# shield-p1000.net
KiCad netlist of a schematic drawn in EAGLE
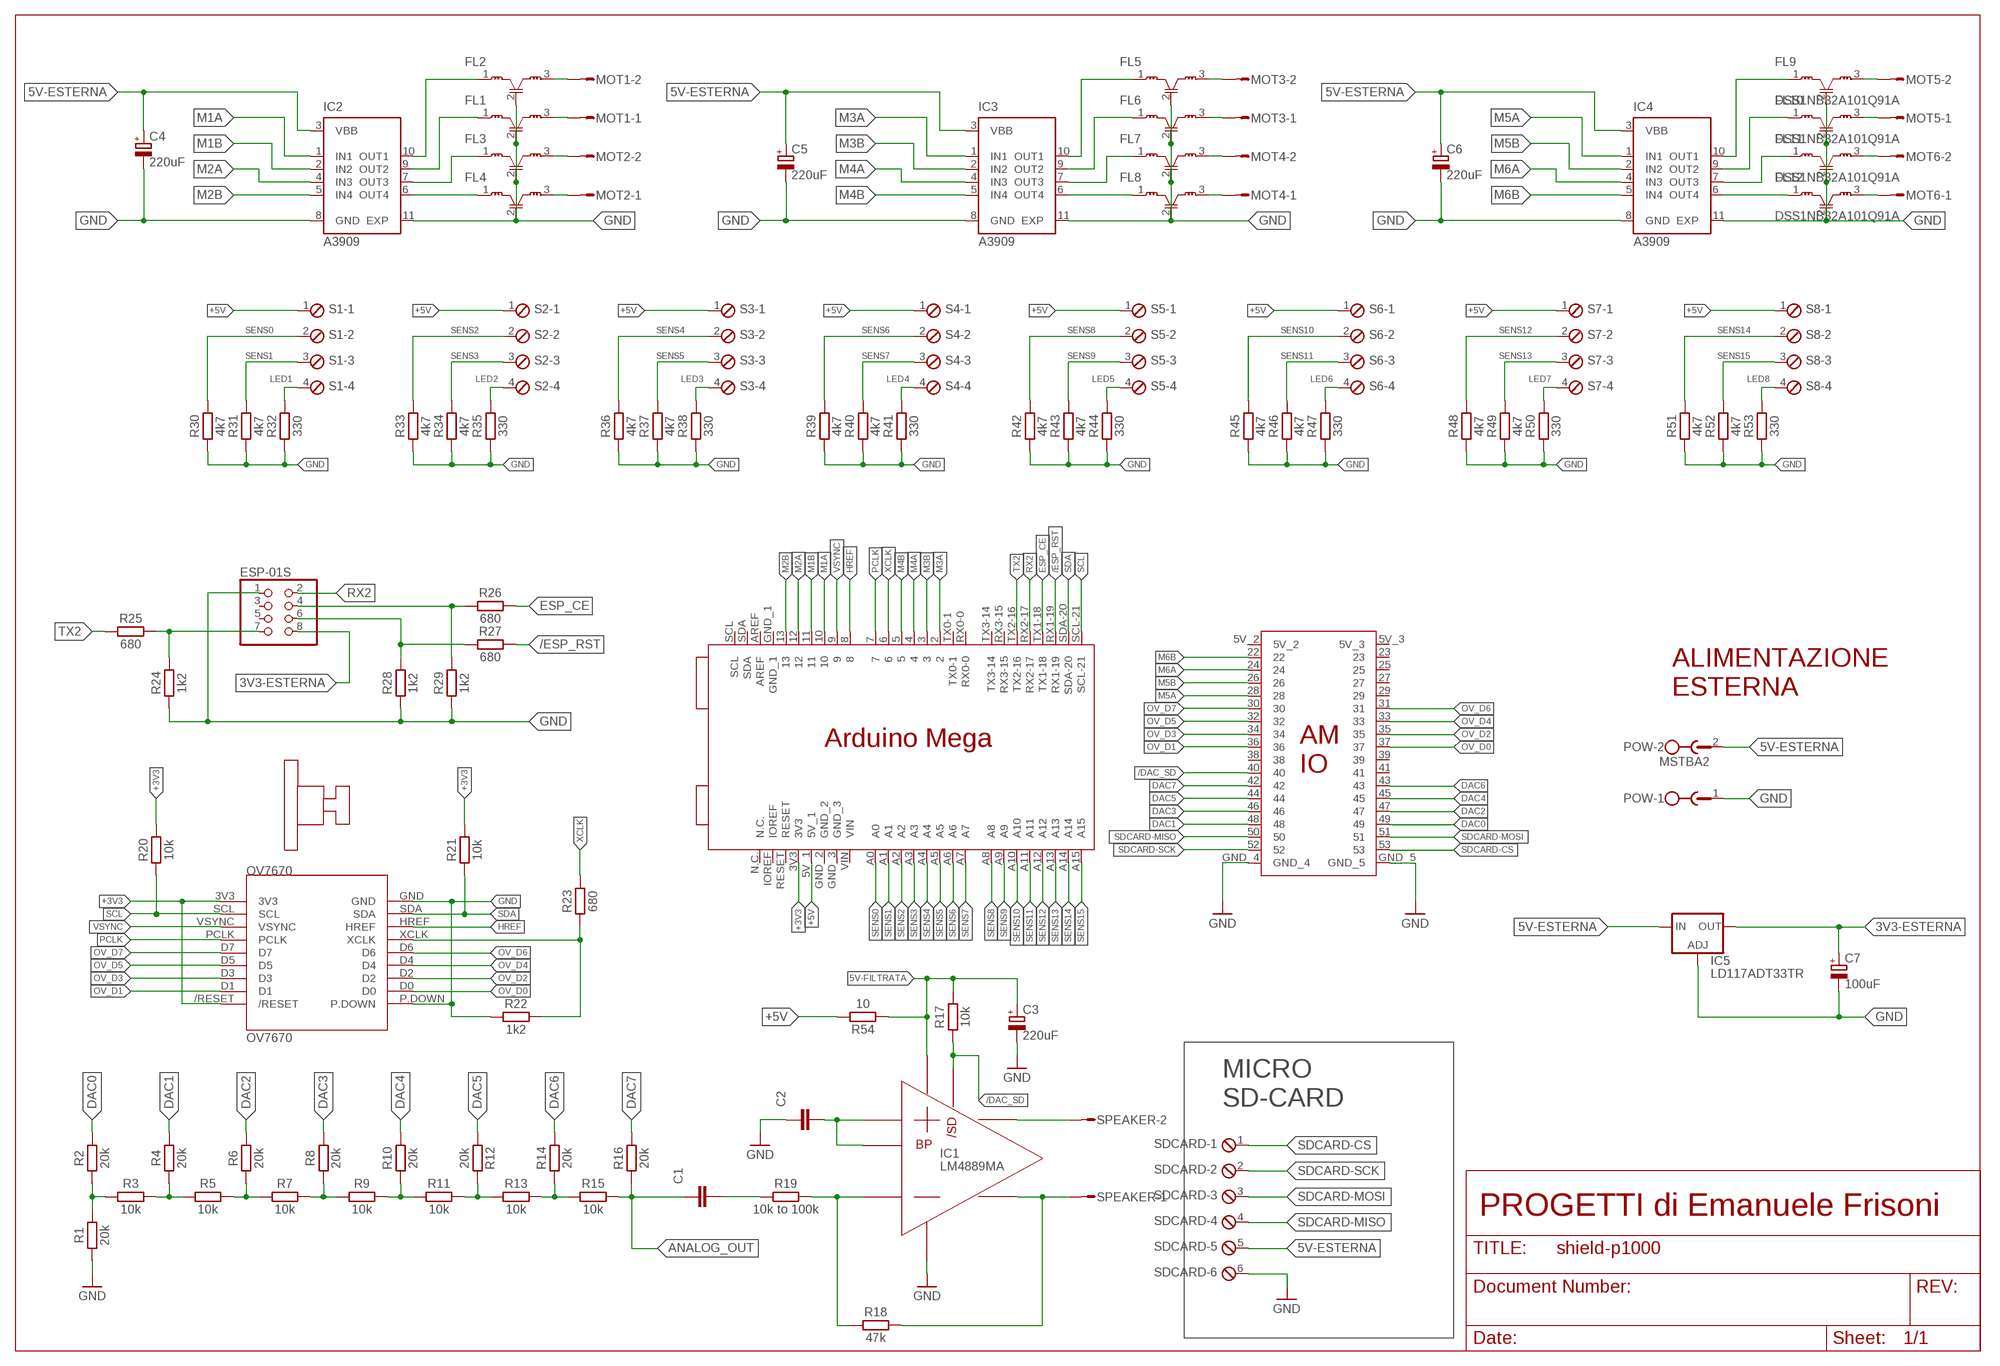
[diagram p0: schematic, sheet 1]

(export (version "E")
  (design (tool "Eeschema 10.0.6"))
  (components
    (comp (ref "ARDUINO-MEGA1")
      (value "ARDUINO-MEGA-SH")
      (footprint "eagle-import:ARDUINO-MEGA-SH")
      (libsource (lib "eagle-import") (part "ARDUINO-MEGA-SH"))
    )
    (comp (ref "C1")
      (value "1uF")
      (footprint "eagle-import:CAPC1608X85")
      (libsource (lib "eagle-import") (part "CCHIP-0603(1608-METRIC)_"))
    )
    (comp (ref "C2")
      (value "1uF")
      (footprint "eagle-import:CAPC1608X85")
      (libsource (lib "eagle-import") (part "CCHIP-0603(1608-METRIC)_"))
    )
    (comp (ref "C3")
      (value "220uF")
      (footprint "eagle-import:E3,5-10")
      (libsource (lib "eagle-import") (part "CPOL-EUE3.5-10"))
    )
    (comp (ref "C4")
      (value "220uF")
      (footprint "eagle-import:E3,5-10")
      (libsource (lib "eagle-import") (part "CPOL-EUE3.5-10"))
    )
    (comp (ref "C5")
      (value "220uF")
      (footprint "eagle-import:E3,5-10")
      (libsource (lib "eagle-import") (part "CPOL-EUE3.5-10"))
    )
    (comp (ref "C6")
      (value "220uF")
      (footprint "eagle-import:E3,5-10")
      (libsource (lib "eagle-import") (part "CPOL-EUE3.5-10"))
    )
    (comp (ref "C7")
      (value "100uF")
      (footprint "eagle-import:E3,5-10")
      (libsource (lib "eagle-import") (part "CPOL-EUE3.5-10"))
    )
    (comp (ref "ESP-01S")
      (value "PINHD-2X4")
      (footprint "eagle-import:2X04")
      (libsource (lib "eagle-import") (part "PINHD-2X4"))
    )
    (comp (ref "FL1")
      (value "DSS1NB32A101Q91A")
      (footprint "eagle-import:RADIAL-3")
      (fields (field (name "MANUFACTURER") "Murata Electronics") (field (name "CREATED_BY") "PCBLayout.com"))
      (libsource (lib "eagle-import") (part "DSS1NB32A101Q91A"))
    )
    (comp (ref "FL2")
      (value "DSS1NB32A101Q91A")
      (footprint "eagle-import:RADIAL-3")
      (fields (field (name "MANUFACTURER") "Murata Electronics") (field (name "CREATED_BY") "PCBLayout.com"))
      (libsource (lib "eagle-import") (part "DSS1NB32A101Q91A"))
    )
    (comp (ref "FL3")
      (value "DSS1NB32A101Q91A")
      (footprint "eagle-import:RADIAL-3")
      (fields (field (name "MANUFACTURER") "Murata Electronics") (field (name "CREATED_BY") "PCBLayout.com"))
      (libsource (lib "eagle-import") (part "DSS1NB32A101Q91A"))
    )
    (comp (ref "FL4")
      (value "DSS1NB32A101Q91A")
      (footprint "eagle-import:RADIAL-3")
      (fields (field (name "MANUFACTURER") "Murata Electronics") (field (name "CREATED_BY") "PCBLayout.com"))
      (libsource (lib "eagle-import") (part "DSS1NB32A101Q91A"))
    )
    (comp (ref "FL5")
      (value "DSS1NB32A101Q91A")
      (footprint "eagle-import:RADIAL-3")
      (fields (field (name "MANUFACTURER") "Murata Electronics") (field (name "CREATED_BY") "PCBLayout.com"))
      (libsource (lib "eagle-import") (part "DSS1NB32A101Q91A"))
    )
    (comp (ref "FL6")
      (value "DSS1NB32A101Q91A")
      (footprint "eagle-import:RADIAL-3")
      (fields (field (name "MANUFACTURER") "Murata Electronics") (field (name "CREATED_BY") "PCBLayout.com"))
      (libsource (lib "eagle-import") (part "DSS1NB32A101Q91A"))
    )
    (comp (ref "FL7")
      (value "DSS1NB32A101Q91A")
      (footprint "eagle-import:RADIAL-3")
      (fields (field (name "MANUFACTURER") "Murata Electronics") (field (name "CREATED_BY") "PCBLayout.com"))
      (libsource (lib "eagle-import") (part "DSS1NB32A101Q91A"))
    )
    (comp (ref "FL8")
      (value "DSS1NB32A101Q91A")
      (footprint "eagle-import:RADIAL-3")
      (fields (field (name "MANUFACTURER") "Murata Electronics") (field (name "CREATED_BY") "PCBLayout.com"))
      (libsource (lib "eagle-import") (part "DSS1NB32A101Q91A"))
    )
    (comp (ref "FL9")
      (value "DSS1NB32A101Q91A")
      (footprint "eagle-import:RADIAL-3")
      (fields (field (name "MANUFACTURER") "Murata Electronics") (field (name "CREATED_BY") "PCBLayout.com"))
      (libsource (lib "eagle-import") (part "DSS1NB32A101Q91A"))
    )
    (comp (ref "FL10")
      (value "DSS1NB32A101Q91A")
      (footprint "eagle-import:RADIAL-3")
      (fields (field (name "MANUFACTURER") "Murata Electronics") (field (name "CREATED_BY") "PCBLayout.com"))
      (libsource (lib "eagle-import") (part "DSS1NB32A101Q91A"))
    )
    (comp (ref "FL11")
      (value "DSS1NB32A101Q91A")
      (footprint "eagle-import:RADIAL-3")
      (fields (field (name "MANUFACTURER") "Murata Electronics") (field (name "CREATED_BY") "PCBLayout.com"))
      (libsource (lib "eagle-import") (part "DSS1NB32A101Q91A"))
    )
    (comp (ref "FL12")
      (value "DSS1NB32A101Q91A")
      (footprint "eagle-import:RADIAL-3")
      (fields (field (name "MANUFACTURER") "Murata Electronics") (field (name "CREATED_BY") "PCBLayout.com"))
      (libsource (lib "eagle-import") (part "DSS1NB32A101Q91A"))
    )
    (comp (ref "IC1")
      (value "LM4889MA")
      (footprint "eagle-import:SOIC127P599X175-8N")
      (libsource (lib "eagle-import") (part "LM4889MA"))
    )
    (comp (ref "IC2")
      (value "A3909")
      (footprint "eagle-import:10-MSOP")
      (libsource (lib "eagle-import") (part "A3909LY"))
    )
    (comp (ref "IC3")
      (value "A3909")
      (footprint "eagle-import:10-MSOP")
      (libsource (lib "eagle-import") (part "A3909LY"))
    )
    (comp (ref "IC4")
      (value "A3909")
      (footprint "eagle-import:10-MSOP")
      (libsource (lib "eagle-import") (part "A3909LY"))
    )
    (comp (ref "IC5")
      (value "LD117ADT33TR")
      (footprint "eagle-import:DPACK")
      (libsource (lib "eagle-import") (part "LD117A?DT33TR"))
    )
    (comp (ref "MOT1")
      (value "S02P")
      (footprint "eagle-import:S02P")
      (libsource (lib "eagle-import") (part "S02P"))
    )
    (comp (ref "MOT2")
      (value "S02P")
      (footprint "eagle-import:S02P")
      (libsource (lib "eagle-import") (part "S02P"))
    )
    (comp (ref "MOT3")
      (value "S02P")
      (footprint "eagle-import:S02P")
      (libsource (lib "eagle-import") (part "S02P"))
    )
    (comp (ref "MOT4")
      (value "S02P")
      (footprint "eagle-import:S02P")
      (libsource (lib "eagle-import") (part "S02P"))
    )
    (comp (ref "MOT5")
      (value "S02P")
      (footprint "eagle-import:S02P")
      (libsource (lib "eagle-import") (part "S02P"))
    )
    (comp (ref "MOT6")
      (value "S02P")
      (footprint "eagle-import:S02P")
      (libsource (lib "eagle-import") (part "S02P"))
    )
    (comp (ref "OV7670")
      (value "OV7670")
      (footprint "eagle-import:OV7670-HEADER")
      (libsource (lib "eagle-import") (part "OV7670"))
    )
    (comp (ref "POW")
      (value "MSTBA2")
      (footprint "eagle-import:MSTBA2")
      (fields (field (name "MF") "FARNELL") (field (name "MPN") "1757242"))
      (libsource (lib "eagle-import") (part "MSTBA2"))
    )
    (comp (ref "R1")
      (value "20k")
      (footprint "eagle-import:RESC1608X60")
      (libsource (lib "eagle-import") (part "RCHIP-0603(1608-METRIC)_"))
    )
    (comp (ref "R2")
      (value "20k")
      (footprint "eagle-import:RESC1608X60")
      (libsource (lib "eagle-import") (part "RCHIP-0603(1608-METRIC)_"))
    )
    (comp (ref "R3")
      (value "10k")
      (footprint "eagle-import:RESC1608X60")
      (libsource (lib "eagle-import") (part "RCHIP-0603(1608-METRIC)_"))
    )
    (comp (ref "R4")
      (value "20k")
      (footprint "eagle-import:RESC1608X60")
      (libsource (lib "eagle-import") (part "RCHIP-0603(1608-METRIC)_"))
    )
    (comp (ref "R5")
      (value "10k")
      (footprint "eagle-import:RESC1608X60")
      (libsource (lib "eagle-import") (part "RCHIP-0603(1608-METRIC)_"))
    )
    (comp (ref "R6")
      (value "20k")
      (footprint "eagle-import:RESC1608X60")
      (libsource (lib "eagle-import") (part "RCHIP-0603(1608-METRIC)_"))
    )
    (comp (ref "R7")
      (value "10k")
      (footprint "eagle-import:RESC1608X60")
      (libsource (lib "eagle-import") (part "RCHIP-0603(1608-METRIC)_"))
    )
    (comp (ref "R8")
      (value "20k")
      (footprint "eagle-import:RESC1608X60")
      (libsource (lib "eagle-import") (part "RCHIP-0603(1608-METRIC)_"))
    )
    (comp (ref "R9")
      (value "10k")
      (footprint "eagle-import:RESC1608X60")
      (libsource (lib "eagle-import") (part "RCHIP-0603(1608-METRIC)_"))
    )
    (comp (ref "R10")
      (value "20k")
      (footprint "eagle-import:RESC1608X60")
      (libsource (lib "eagle-import") (part "RCHIP-0603(1608-METRIC)_"))
    )
    (comp (ref "R11")
      (value "10k")
      (footprint "eagle-import:RESC1608X60")
      (libsource (lib "eagle-import") (part "RCHIP-0603(1608-METRIC)_"))
    )
    (comp (ref "R12")
      (value "20k")
      (footprint "eagle-import:RESC1608X60")
      (libsource (lib "eagle-import") (part "RCHIP-0603(1608-METRIC)_"))
    )
    (comp (ref "R13")
      (value "10k")
      (footprint "eagle-import:RESC1608X60")
      (libsource (lib "eagle-import") (part "RCHIP-0603(1608-METRIC)_"))
    )
    (comp (ref "R14")
      (value "20k")
      (footprint "eagle-import:RESC1608X60")
      (libsource (lib "eagle-import") (part "RCHIP-0603(1608-METRIC)_"))
    )
    (comp (ref "R15")
      (value "10k")
      (footprint "eagle-import:RESC1608X60")
      (libsource (lib "eagle-import") (part "RCHIP-0603(1608-METRIC)_"))
    )
    (comp (ref "R16")
      (value "20k")
      (footprint "eagle-import:RESC1608X60")
      (libsource (lib "eagle-import") (part "RCHIP-0603(1608-METRIC)_"))
    )
    (comp (ref "R17")
      (value "10k")
      (footprint "eagle-import:RESC1608X60")
      (libsource (lib "eagle-import") (part "RCHIP-0603(1608-METRIC)_"))
    )
    (comp (ref "R18")
      (value "47k")
      (footprint "eagle-import:RESC1608X60")
      (libsource (lib "eagle-import") (part "RCHIP-0603(1608-METRIC)_"))
    )
    (comp (ref "R19")
      (value "10k to 100k")
      (footprint "eagle-import:RESAD724W46L381D178B")
      (libsource (lib "eagle-import") (part "RAXIAL-7.2MM-PITCH_"))
    )
    (comp (ref "R20")
      (value "10k")
      (footprint "eagle-import:RESC1608X60")
      (libsource (lib "eagle-import") (part "RCHIP-0603(1608-METRIC)_"))
    )
    (comp (ref "R21")
      (value "10k")
      (footprint "eagle-import:RESC1608X60")
      (libsource (lib "eagle-import") (part "RCHIP-0603(1608-METRIC)_"))
    )
    (comp (ref "R22")
      (value "1k2")
      (footprint "eagle-import:RESC1608X60")
      (libsource (lib "eagle-import") (part "RCHIP-0603(1608-METRIC)_"))
    )
    (comp (ref "R23")
      (value "680")
      (footprint "eagle-import:RESC1608X60")
      (libsource (lib "eagle-import") (part "RCHIP-0603(1608-METRIC)_"))
    )
    (comp (ref "R24")
      (value "1k2")
      (footprint "eagle-import:RESC1608X60")
      (libsource (lib "eagle-import") (part "RCHIP-0603(1608-METRIC)_"))
    )
    (comp (ref "R25")
      (value "680")
      (footprint "eagle-import:RESC1608X60")
      (libsource (lib "eagle-import") (part "RCHIP-0603(1608-METRIC)_"))
    )
    (comp (ref "R26")
      (value "680")
      (footprint "eagle-import:RESC1608X60")
      (libsource (lib "eagle-import") (part "RCHIP-0603(1608-METRIC)_"))
    )
    (comp (ref "R27")
      (value "680")
      (footprint "eagle-import:RESC1608X60")
      (libsource (lib "eagle-import") (part "RCHIP-0603(1608-METRIC)_"))
    )
    (comp (ref "R28")
      (value "1k2")
      (footprint "eagle-import:RESC1608X60")
      (libsource (lib "eagle-import") (part "RCHIP-0603(1608-METRIC)_"))
    )
    (comp (ref "R29")
      (value "1k2")
      (footprint "eagle-import:RESC1608X60")
      (libsource (lib "eagle-import") (part "RCHIP-0603(1608-METRIC)_"))
    )
    (comp (ref "R30")
      (value "4k7")
      (footprint "eagle-import:RESC1608X60")
      (libsource (lib "eagle-import") (part "RCHIP-0603(1608-METRIC)_"))
    )
    (comp (ref "R31")
      (value "4k7")
      (footprint "eagle-import:RESC1608X60")
      (libsource (lib "eagle-import") (part "RCHIP-0603(1608-METRIC)_"))
    )
    (comp (ref "R32")
      (value "330")
      (footprint "eagle-import:RESC1608X60")
      (libsource (lib "eagle-import") (part "RCHIP-0603(1608-METRIC)_"))
    )
    (comp (ref "R33")
      (value "4k7")
      (footprint "eagle-import:RESC1608X60")
      (libsource (lib "eagle-import") (part "RCHIP-0603(1608-METRIC)_"))
    )
    (comp (ref "R34")
      (value "4k7")
      (footprint "eagle-import:RESC1608X60")
      (libsource (lib "eagle-import") (part "RCHIP-0603(1608-METRIC)_"))
    )
    (comp (ref "R35")
      (value "330")
      (footprint "eagle-import:RESC1608X60")
      (libsource (lib "eagle-import") (part "RCHIP-0603(1608-METRIC)_"))
    )
    (comp (ref "R36")
      (value "4k7")
      (footprint "eagle-import:RESC1608X60")
      (libsource (lib "eagle-import") (part "RCHIP-0603(1608-METRIC)_"))
    )
    (comp (ref "R37")
      (value "4k7")
      (footprint "eagle-import:RESC1608X60")
      (libsource (lib "eagle-import") (part "RCHIP-0603(1608-METRIC)_"))
    )
    (comp (ref "R38")
      (value "330")
      (footprint "eagle-import:RESC1608X60")
      (libsource (lib "eagle-import") (part "RCHIP-0603(1608-METRIC)_"))
    )
    (comp (ref "R39")
      (value "4k7")
      (footprint "eagle-import:RESC1608X60")
      (libsource (lib "eagle-import") (part "RCHIP-0603(1608-METRIC)_"))
    )
    (comp (ref "R40")
      (value "4k7")
      (footprint "eagle-import:RESC1608X60")
      (libsource (lib "eagle-import") (part "RCHIP-0603(1608-METRIC)_"))
    )
    (comp (ref "R41")
      (value "330")
      (footprint "eagle-import:RESC1608X60")
      (libsource (lib "eagle-import") (part "RCHIP-0603(1608-METRIC)_"))
    )
    (comp (ref "R42")
      (value "4k7")
      (footprint "eagle-import:RESC1608X60")
      (libsource (lib "eagle-import") (part "RCHIP-0603(1608-METRIC)_"))
    )
    (comp (ref "R43")
      (value "4k7")
      (footprint "eagle-import:RESC1608X60")
      (libsource (lib "eagle-import") (part "RCHIP-0603(1608-METRIC)_"))
    )
    (comp (ref "R44")
      (value "330")
      (footprint "eagle-import:RESC1608X60")
      (libsource (lib "eagle-import") (part "RCHIP-0603(1608-METRIC)_"))
    )
    (comp (ref "R45")
      (value "4k7")
      (footprint "eagle-import:RESC1608X60")
      (libsource (lib "eagle-import") (part "RCHIP-0603(1608-METRIC)_"))
    )
    (comp (ref "R46")
      (value "4k7")
      (footprint "eagle-import:RESC1608X60")
      (libsource (lib "eagle-import") (part "RCHIP-0603(1608-METRIC)_"))
    )
    (comp (ref "R47")
      (value "330")
      (footprint "eagle-import:RESC1608X60")
      (libsource (lib "eagle-import") (part "RCHIP-0603(1608-METRIC)_"))
    )
    (comp (ref "R48")
      (value "4k7")
      (footprint "eagle-import:RESC1608X60")
      (libsource (lib "eagle-import") (part "RCHIP-0603(1608-METRIC)_"))
    )
    (comp (ref "R49")
      (value "4k7")
      (footprint "eagle-import:RESC1608X60")
      (libsource (lib "eagle-import") (part "RCHIP-0603(1608-METRIC)_"))
    )
    (comp (ref "R50")
      (value "330")
      (footprint "eagle-import:RESC1608X60")
      (libsource (lib "eagle-import") (part "RCHIP-0603(1608-METRIC)_"))
    )
    (comp (ref "R51")
      (value "4k7")
      (footprint "eagle-import:RESC1608X60")
      (libsource (lib "eagle-import") (part "RCHIP-0603(1608-METRIC)_"))
    )
    (comp (ref "R52")
      (value "4k7")
      (footprint "eagle-import:RESC1608X60")
      (libsource (lib "eagle-import") (part "RCHIP-0603(1608-METRIC)_"))
    )
    (comp (ref "R53")
      (value "330")
      (footprint "eagle-import:RESC1608X60")
      (libsource (lib "eagle-import") (part "RCHIP-0603(1608-METRIC)_"))
    )
    (comp (ref "R54")
      (value "10")
      (footprint "eagle-import:RESC1608X60")
      (libsource (lib "eagle-import") (part "RCHIP-0603(1608-METRIC)_"))
    )
    (comp (ref "S1")
      (value "MPT4")
      (footprint "eagle-import:4POL254")
      (libsource (lib "eagle-import") (part "MPT4"))
    )
    (comp (ref "S2")
      (value "MPT4")
      (footprint "eagle-import:4POL254")
      (libsource (lib "eagle-import") (part "MPT4"))
    )
    (comp (ref "S3")
      (value "MPT4")
      (footprint "eagle-import:4POL254")
      (libsource (lib "eagle-import") (part "MPT4"))
    )
    (comp (ref "S4")
      (value "MPT4")
      (footprint "eagle-import:4POL254")
      (libsource (lib "eagle-import") (part "MPT4"))
    )
    (comp (ref "S5")
      (value "MPT4")
      (footprint "eagle-import:4POL254")
      (libsource (lib "eagle-import") (part "MPT4"))
    )
    (comp (ref "S6")
      (value "MPT4")
      (footprint "eagle-import:4POL254")
      (libsource (lib "eagle-import") (part "MPT4"))
    )
    (comp (ref "S7")
      (value "MPT4")
      (footprint "eagle-import:4POL254")
      (libsource (lib "eagle-import") (part "MPT4"))
    )
    (comp (ref "S8")
      (value "MPT4")
      (footprint "eagle-import:4POL254")
      (libsource (lib "eagle-import") (part "MPT4"))
    )
    (comp (ref "SDCARD")
      (value "MPT6")
      (footprint "eagle-import:6POL254")
      (libsource (lib "eagle-import") (part "MPT6"))
    )
    (comp (ref "SPEAKER")
      (value "S02P")
      (footprint "eagle-import:S02P")
      (libsource (lib "eagle-import") (part "S02P"))
    )
  )
  (nets
    (net (code "1") (name "+3V3") (class "Default")
      (node (ref "ARDUINO-MEGA1") (pin "3V3") (pinfunction "3V3_3V3") (pintype "bidirectional"))
      (node (ref "OV7670") (pin "/RESET") (pinfunction "/RESET_/RESET") (pintype "bidirectional"))
      (node (ref "OV7670") (pin "3V3") (pinfunction "3V3_3V3") (pintype "bidirectional"))
      (node (ref "R20") (pin "2") (pinfunction "2_2") (pintype "passive"))
      (node (ref "R21") (pin "2") (pinfunction "2_2") (pintype "passive"))
    )
    (net (code "2") (name "+5V") (class "Default")
      (node (ref "ARDUINO-MEGA1") (pin "5V_1") (pinfunction "5V_1_5V_1") (pintype "bidirectional"))
      (node (ref "R54") (pin "1") (pinfunction "1_1") (pintype "passive"))
      (node (ref "S1") (pin "1") (pinfunction "1_1") (pintype "passive"))
      (node (ref "S2") (pin "1") (pinfunction "1_1") (pintype "passive"))
      (node (ref "S3") (pin "1") (pinfunction "1_1") (pintype "passive"))
      (node (ref "S4") (pin "1") (pinfunction "1_1") (pintype "passive"))
      (node (ref "S5") (pin "1") (pinfunction "1_1") (pintype "passive"))
      (node (ref "S6") (pin "1") (pinfunction "1_1") (pintype "passive"))
      (node (ref "S7") (pin "1") (pinfunction "1_1") (pintype "passive"))
      (node (ref "S8") (pin "1") (pinfunction "1_1") (pintype "passive"))
    )
    (net (code "3") (name "/LED1") (class "Default")
      (node (ref "R32") (pin "2") (pinfunction "2_2") (pintype "passive"))
      (node (ref "S1") (pin "4") (pinfunction "1_4") (pintype "passive"))
    )
    (net (code "4") (name "/LED2") (class "Default")
      (node (ref "R35") (pin "2") (pinfunction "2_2") (pintype "passive"))
      (node (ref "S2") (pin "4") (pinfunction "1_4") (pintype "passive"))
    )
    (net (code "5") (name "/LED3") (class "Default")
      (node (ref "R38") (pin "2") (pinfunction "2_2") (pintype "passive"))
      (node (ref "S3") (pin "4") (pinfunction "1_4") (pintype "passive"))
    )
    (net (code "6") (name "/LED4") (class "Default")
      (node (ref "R41") (pin "2") (pinfunction "2_2") (pintype "passive"))
      (node (ref "S4") (pin "4") (pinfunction "1_4") (pintype "passive"))
    )
    (net (code "7") (name "/LED5") (class "Default")
      (node (ref "R44") (pin "2") (pinfunction "2_2") (pintype "passive"))
      (node (ref "S5") (pin "4") (pinfunction "1_4") (pintype "passive"))
    )
    (net (code "8") (name "/LED6") (class "Default")
      (node (ref "R47") (pin "2") (pinfunction "2_2") (pintype "passive"))
      (node (ref "S6") (pin "4") (pinfunction "1_4") (pintype "passive"))
    )
    (net (code "9") (name "/LED7") (class "Default")
      (node (ref "R50") (pin "2") (pinfunction "2_2") (pintype "passive"))
      (node (ref "S7") (pin "4") (pinfunction "1_4") (pintype "passive"))
    )
    (net (code "10") (name "/LED8") (class "Default")
      (node (ref "R53") (pin "2") (pinfunction "2_2") (pintype "passive"))
      (node (ref "S8") (pin "4") (pinfunction "1_4") (pintype "passive"))
    )
    (net (code "11") (name "3V3-ESTERNA") (class "Default")
      (node (ref "C7") (pin "+") (pinfunction "+_+") (pintype "passive"))
      (node (ref "ESP-01S") (pin "8") (pinfunction "8_8") (pintype "passive"))
      (node (ref "IC5") (pin "4") (pinfunction "OUT_4") (pintype "passive"))
    )
    (net (code "12") (name "5V-ESTERNA") (class "Default")
      (node (ref "C4") (pin "+") (pinfunction "+_+") (pintype "passive"))
      (node (ref "C5") (pin "+") (pinfunction "+_+") (pintype "passive"))
      (node (ref "C6") (pin "+") (pinfunction "+_+") (pintype "passive"))
      (node (ref "IC2") (pin "3") (pinfunction "VBB_3") (pintype "power_in"))
      (node (ref "IC3") (pin "3") (pinfunction "VBB_3") (pintype "power_in"))
      (node (ref "IC4") (pin "3") (pinfunction "VBB_3") (pintype "power_in"))
      (node (ref "IC5") (pin "3") (pinfunction "IN_3") (pintype "input"))
      (node (ref "POW") (pin "2") (pinfunction "1_2") (pintype "passive"))
      (node (ref "SDCARD") (pin "5") (pinfunction "1_5") (pintype "passive"))
    )
    (net (code "13") (name "5V-FILTRATA") (class "Default")
      (node (ref "C3") (pin "+") (pinfunction "+_+") (pintype "passive"))
      (node (ref "IC1") (pin "6") (pinfunction "VDD_6") (pintype "bidirectional"))
      (node (ref "R17") (pin "1") (pinfunction "1_1") (pintype "passive"))
      (node (ref "R54") (pin "2") (pinfunction "2_2") (pintype "passive"))
    )
    (net (code "14") (name "ANALOG_OUT") (class "Default")
      (node (ref "C1") (pin "1") (pinfunction "1_1") (pintype "passive"))
      (node (ref "R15") (pin "1") (pinfunction "1_1") (pintype "passive"))
      (node (ref "R16") (pin "2") (pinfunction "2_2") (pintype "passive"))
    )
    (net (code "15") (name "DAC0") (class "Default")
      (node (ref "ARDUINO-MEGA1") (pin "49") (pinfunction "49_49") (pintype "bidirectional"))
      (node (ref "R2") (pin "1") (pinfunction "1_1") (pintype "passive"))
    )
    (net (code "16") (name "DAC1") (class "Default")
      (node (ref "ARDUINO-MEGA1") (pin "48") (pinfunction "48_48") (pintype "bidirectional"))
      (node (ref "R4") (pin "1") (pinfunction "1_1") (pintype "passive"))
    )
    (net (code "17") (name "DAC2") (class "Default")
      (node (ref "ARDUINO-MEGA1") (pin "47") (pinfunction "47_47") (pintype "bidirectional"))
      (node (ref "R6") (pin "1") (pinfunction "1_1") (pintype "passive"))
    )
    (net (code "18") (name "DAC3") (class "Default")
      (node (ref "ARDUINO-MEGA1") (pin "46") (pinfunction "46_46") (pintype "bidirectional"))
      (node (ref "R8") (pin "1") (pinfunction "1_1") (pintype "passive"))
    )
    (net (code "19") (name "DAC4") (class "Default")
      (node (ref "ARDUINO-MEGA1") (pin "45") (pinfunction "45_45") (pintype "bidirectional"))
      (node (ref "R10") (pin "1") (pinfunction "1_1") (pintype "passive"))
    )
    (net (code "20") (name "DAC5") (class "Default")
      (node (ref "ARDUINO-MEGA1") (pin "44") (pinfunction "44_44") (pintype "bidirectional"))
      (node (ref "R12") (pin "1") (pinfunction "1_1") (pintype "passive"))
    )
    (net (code "21") (name "DAC6") (class "Default")
      (node (ref "ARDUINO-MEGA1") (pin "43") (pinfunction "43_43") (pintype "bidirectional"))
      (node (ref "R14") (pin "1") (pinfunction "1_1") (pintype "passive"))
    )
    (net (code "22") (name "DAC7") (class "Default")
      (node (ref "ARDUINO-MEGA1") (pin "42") (pinfunction "42_42") (pintype "bidirectional"))
      (node (ref "R16") (pin "1") (pinfunction "1_1") (pintype "passive"))
    )
    (net (code "23") (name "ESP_CE") (class "Default")
      (node (ref "ARDUINO-MEGA1") (pin "TX1-18") (pinfunction "TX1-18_TX1-18") (pintype "bidirectional"))
      (node (ref "R26") (pin "2") (pinfunction "2_2") (pintype "passive"))
    )
    (net (code "24") (name "GND") (class "Default")
      (node (ref "ARDUINO-MEGA1") (pin "GND_4") (pinfunction "GND_4_GND_4") (pintype "bidirectional"))
      (node (ref "ARDUINO-MEGA1") (pin "GND_5") (pinfunction "GND_5_GND_5") (pintype "bidirectional"))
      (node (ref "C2") (pin "1") (pinfunction "1_1") (pintype "passive"))
      (node (ref "C3") (pin "-") (pinfunction "-_-") (pintype "passive"))
      (node (ref "C4") (pin "-") (pinfunction "-_-") (pintype "passive"))
      (node (ref "C5") (pin "-") (pinfunction "-_-") (pintype "passive"))
      (node (ref "C6") (pin "-") (pinfunction "-_-") (pintype "passive"))
      (node (ref "C7") (pin "-") (pinfunction "-_-") (pintype "passive"))
      (node (ref "ESP-01S") (pin "1") (pinfunction "1_1") (pintype "passive"))
      (node (ref "FL1") (pin "2") (pinfunction "GND_2") (pintype "passive"))
      (node (ref "FL10") (pin "2") (pinfunction "GND_2") (pintype "passive"))
      (node (ref "FL11") (pin "2") (pinfunction "GND_2") (pintype "passive"))
      (node (ref "FL12") (pin "2") (pinfunction "GND_2") (pintype "passive"))
      (node (ref "FL2") (pin "2") (pinfunction "GND_2") (pintype "passive"))
      (node (ref "FL3") (pin "2") (pinfunction "GND_2") (pintype "passive"))
      (node (ref "FL4") (pin "2") (pinfunction "GND_2") (pintype "passive"))
      (node (ref "FL5") (pin "2") (pinfunction "GND_2") (pintype "passive"))
      (node (ref "FL6") (pin "2") (pinfunction "GND_2") (pintype "passive"))
      (node (ref "FL7") (pin "2") (pinfunction "GND_2") (pintype "passive"))
      (node (ref "FL8") (pin "2") (pinfunction "GND_2") (pintype "passive"))
      (node (ref "FL9") (pin "2") (pinfunction "GND_2") (pintype "passive"))
      (node (ref "IC1") (pin "7") (pinfunction "VSS_7") (pintype "bidirectional"))
      (node (ref "IC2") (pin "11") (pinfunction "EXP_11") (pintype "passive"))
      (node (ref "IC2") (pin "8") (pinfunction "GND_8") (pintype "power_in"))
      (node (ref "IC3") (pin "11") (pinfunction "EXP_11") (pintype "passive"))
      (node (ref "IC3") (pin "8") (pinfunction "GND_8") (pintype "power_in"))
      (node (ref "IC4") (pin "11") (pinfunction "EXP_11") (pintype "passive"))
      (node (ref "IC4") (pin "8") (pinfunction "GND_8") (pintype "power_in"))
      (node (ref "IC5") (pin "1") (pinfunction "ADJ_1") (pintype "input"))
      (node (ref "OV7670") (pin "GND") (pinfunction "GND_GND") (pintype "bidirectional"))
      (node (ref "OV7670") (pin "P.DOWN") (pinfunction "P.DOWN_P.DOWN") (pintype "bidirectional"))
      (node (ref "POW") (pin "1") (pinfunction "1_1") (pintype "passive"))
      (node (ref "R1") (pin "1") (pinfunction "1_1") (pintype "passive"))
      (node (ref "R22") (pin "1") (pinfunction "1_1") (pintype "passive"))
      (node (ref "R24") (pin "1") (pinfunction "1_1") (pintype "passive"))
      (node (ref "R28") (pin "1") (pinfunction "1_1") (pintype "passive"))
      (node (ref "R29") (pin "1") (pinfunction "1_1") (pintype "passive"))
      (node (ref "R30") (pin "1") (pinfunction "1_1") (pintype "passive"))
      (node (ref "R31") (pin "1") (pinfunction "1_1") (pintype "passive"))
      (node (ref "R32") (pin "1") (pinfunction "1_1") (pintype "passive"))
      (node (ref "R33") (pin "1") (pinfunction "1_1") (pintype "passive"))
      (node (ref "R34") (pin "1") (pinfunction "1_1") (pintype "passive"))
      (node (ref "R35") (pin "1") (pinfunction "1_1") (pintype "passive"))
      (node (ref "R36") (pin "1") (pinfunction "1_1") (pintype "passive"))
      (node (ref "R37") (pin "1") (pinfunction "1_1") (pintype "passive"))
      (node (ref "R38") (pin "1") (pinfunction "1_1") (pintype "passive"))
      (node (ref "R39") (pin "1") (pinfunction "1_1") (pintype "passive"))
      (node (ref "R40") (pin "1") (pinfunction "1_1") (pintype "passive"))
      (node (ref "R41") (pin "1") (pinfunction "1_1") (pintype "passive"))
      (node (ref "R42") (pin "1") (pinfunction "1_1") (pintype "passive"))
      (node (ref "R43") (pin "1") (pinfunction "1_1") (pintype "passive"))
      (node (ref "R44") (pin "1") (pinfunction "1_1") (pintype "passive"))
      (node (ref "R45") (pin "1") (pinfunction "1_1") (pintype "passive"))
      (node (ref "R46") (pin "1") (pinfunction "1_1") (pintype "passive"))
      (node (ref "R47") (pin "1") (pinfunction "1_1") (pintype "passive"))
      (node (ref "R48") (pin "1") (pinfunction "1_1") (pintype "passive"))
      (node (ref "R49") (pin "1") (pinfunction "1_1") (pintype "passive"))
      (node (ref "R50") (pin "1") (pinfunction "1_1") (pintype "passive"))
      (node (ref "R51") (pin "1") (pinfunction "1_1") (pintype "passive"))
      (node (ref "R52") (pin "1") (pinfunction "1_1") (pintype "passive"))
      (node (ref "R53") (pin "1") (pinfunction "1_1") (pintype "passive"))
      (node (ref "SDCARD") (pin "6") (pinfunction "1_6") (pintype "passive"))
    )
    (net (code "25") (name "HREF") (class "Default")
      (node (ref "ARDUINO-MEGA1") (pin "8") (pinfunction "8_8") (pintype "bidirectional"))
      (node (ref "OV7670") (pin "HREF") (pinfunction "HREF_HREF") (pintype "bidirectional"))
    )
    (net (code "26") (name "M1A") (class "Default")
      (node (ref "ARDUINO-MEGA1") (pin "10") (pinfunction "10_10") (pintype "bidirectional"))
      (node (ref "IC2") (pin "1") (pinfunction "IN1_1") (pintype "input"))
    )
    (net (code "27") (name "M1B") (class "Default")
      (node (ref "ARDUINO-MEGA1") (pin "11") (pinfunction "11_11") (pintype "bidirectional"))
      (node (ref "IC2") (pin "2") (pinfunction "IN2_2") (pintype "input"))
    )
    (net (code "28") (name "M2A") (class "Default")
      (node (ref "ARDUINO-MEGA1") (pin "12") (pinfunction "12_12") (pintype "bidirectional"))
      (node (ref "IC2") (pin "4") (pinfunction "IN3_4") (pintype "input"))
    )
    (net (code "29") (name "M2B") (class "Default")
      (node (ref "ARDUINO-MEGA1") (pin "13") (pinfunction "13_13") (pintype "bidirectional"))
      (node (ref "IC2") (pin "5") (pinfunction "IN4_5") (pintype "input"))
    )
    (net (code "30") (name "M3A") (class "Default")
      (node (ref "ARDUINO-MEGA1") (pin "2") (pinfunction "2_2") (pintype "bidirectional"))
      (node (ref "IC3") (pin "1") (pinfunction "IN1_1") (pintype "input"))
    )
    (net (code "31") (name "M3B") (class "Default")
      (node (ref "ARDUINO-MEGA1") (pin "3") (pinfunction "3_3") (pintype "bidirectional"))
      (node (ref "IC3") (pin "2") (pinfunction "IN2_2") (pintype "input"))
    )
    (net (code "32") (name "M4A") (class "Default")
      (node (ref "ARDUINO-MEGA1") (pin "4") (pinfunction "4_4") (pintype "bidirectional"))
      (node (ref "IC3") (pin "4") (pinfunction "IN3_4") (pintype "input"))
    )
    (net (code "33") (name "M4B") (class "Default")
      (node (ref "ARDUINO-MEGA1") (pin "5") (pinfunction "5_5") (pintype "bidirectional"))
      (node (ref "IC3") (pin "5") (pinfunction "IN4_5") (pintype "input"))
    )
    (net (code "34") (name "M5A") (class "Default")
      (node (ref "ARDUINO-MEGA1") (pin "28") (pinfunction "28_28") (pintype "bidirectional"))
      (node (ref "IC4") (pin "1") (pinfunction "IN1_1") (pintype "input"))
    )
    (net (code "35") (name "M5B") (class "Default")
      (node (ref "ARDUINO-MEGA1") (pin "26") (pinfunction "26_26") (pintype "bidirectional"))
      (node (ref "IC4") (pin "2") (pinfunction "IN2_2") (pintype "input"))
    )
    (net (code "36") (name "M6A") (class "Default")
      (node (ref "ARDUINO-MEGA1") (pin "24") (pinfunction "24_24") (pintype "bidirectional"))
      (node (ref "IC4") (pin "4") (pinfunction "IN3_4") (pintype "input"))
    )
    (net (code "37") (name "M6B") (class "Default")
      (node (ref "ARDUINO-MEGA1") (pin "22") (pinfunction "22_22") (pintype "bidirectional"))
      (node (ref "IC4") (pin "5") (pinfunction "IN4_5") (pintype "input"))
    )
    (net (code "38") (name "Net-(C1-Pad2)") (class "Default")
      (node (ref "C1") (pin "2") (pinfunction "2_2") (pintype "passive"))
      (node (ref "R19") (pin "1") (pinfunction "1_1") (pintype "passive"))
    )
    (net (code "39") (name "Net-(ESP-01S-Pad4)") (class "Default")
      (node (ref "ESP-01S") (pin "4") (pinfunction "4_4") (pintype "passive"))
      (node (ref "R26") (pin "1") (pinfunction "1_1") (pintype "passive"))
      (node (ref "R29") (pin "2") (pinfunction "2_2") (pintype "passive"))
    )
    (net (code "40") (name "Net-(ESP-01S-Pad6)") (class "Default")
      (node (ref "ESP-01S") (pin "6") (pinfunction "6_6") (pintype "passive"))
      (node (ref "R27") (pin "1") (pinfunction "1_1") (pintype "passive"))
      (node (ref "R28") (pin "2") (pinfunction "2_2") (pintype "passive"))
    )
    (net (code "41") (name "Net-(ESP-01S-Pad7)") (class "Default")
      (node (ref "ESP-01S") (pin "7") (pinfunction "7_7") (pintype "passive"))
      (node (ref "R24") (pin "2") (pinfunction "2_2") (pintype "passive"))
      (node (ref "R25") (pin "2") (pinfunction "2_2") (pintype "passive"))
    )
    (net (code "42") (name "Net-(IC1-BYPASS)") (class "Default")
      (node (ref "C2") (pin "2") (pinfunction "2_2") (pintype "passive"))
      (node (ref "IC1") (pin "2") (pinfunction "BYPASS_2") (pintype "bidirectional"))
      (node (ref "IC1") (pin "3") (pinfunction "IN+_3") (pintype "bidirectional"))
    )
    (net (code "43") (name "Net-(IC1-IN-)") (class "Default")
      (node (ref "IC1") (pin "4") (pinfunction "IN-_4") (pintype "bidirectional"))
      (node (ref "R18") (pin "2") (pinfunction "2_2") (pintype "passive"))
      (node (ref "R19") (pin "2") (pinfunction "2_2") (pintype "passive"))
    )
    (net (code "44") (name "Net-(IC1-VO1)") (class "Default")
      (node (ref "IC1") (pin "5") (pinfunction "VO1_5") (pintype "bidirectional"))
      (node (ref "R18") (pin "1") (pinfunction "1_1") (pintype "passive"))
      (node (ref "SPEAKER") (pin "1") (pinfunction "S_1") (pintype "passive"))
    )
    (net (code "45") (name "Net-(IC1-VO2)") (class "Default")
      (node (ref "IC1") (pin "8") (pinfunction "VO2_8") (pintype "bidirectional"))
      (node (ref "SPEAKER") (pin "2") (pinfunction "S_2") (pintype "passive"))
    )
    (net (code "46") (name "Net-(IC2-OUT1)") (class "Default")
      (node (ref "FL2") (pin "1") (pinfunction "1_1") (pintype "passive"))
      (node (ref "IC2") (pin "10") (pinfunction "OUT1_10") (pintype "output"))
    )
    (net (code "47") (name "Net-(IC2-OUT2)") (class "Default")
      (node (ref "FL1") (pin "1") (pinfunction "1_1") (pintype "passive"))
      (node (ref "IC2") (pin "9") (pinfunction "OUT2_9") (pintype "output"))
    )
    (net (code "48") (name "Net-(IC2-OUT3)") (class "Default")
      (node (ref "FL3") (pin "1") (pinfunction "1_1") (pintype "passive"))
      (node (ref "IC2") (pin "7") (pinfunction "OUT3_7") (pintype "output"))
    )
    (net (code "49") (name "Net-(IC2-OUT4)") (class "Default")
      (node (ref "FL4") (pin "1") (pinfunction "1_1") (pintype "passive"))
      (node (ref "IC2") (pin "6") (pinfunction "OUT4_6") (pintype "output"))
    )
    (net (code "50") (name "Net-(IC3-OUT1)") (class "Default")
      (node (ref "FL5") (pin "1") (pinfunction "1_1") (pintype "passive"))
      (node (ref "IC3") (pin "10") (pinfunction "OUT1_10") (pintype "output"))
    )
    (net (code "51") (name "Net-(IC3-OUT2)") (class "Default")
      (node (ref "FL6") (pin "1") (pinfunction "1_1") (pintype "passive"))
      (node (ref "IC3") (pin "9") (pinfunction "OUT2_9") (pintype "output"))
    )
    (net (code "52") (name "Net-(IC3-OUT3)") (class "Default")
      (node (ref "FL7") (pin "1") (pinfunction "1_1") (pintype "passive"))
      (node (ref "IC3") (pin "7") (pinfunction "OUT3_7") (pintype "output"))
    )
    (net (code "53") (name "Net-(IC3-OUT4)") (class "Default")
      (node (ref "FL8") (pin "1") (pinfunction "1_1") (pintype "passive"))
      (node (ref "IC3") (pin "6") (pinfunction "OUT4_6") (pintype "output"))
    )
    (net (code "54") (name "Net-(IC4-OUT1)") (class "Default")
      (node (ref "FL9") (pin "1") (pinfunction "1_1") (pintype "passive"))
      (node (ref "IC4") (pin "10") (pinfunction "OUT1_10") (pintype "output"))
    )
    (net (code "55") (name "Net-(IC4-OUT2)") (class "Default")
      (node (ref "FL10") (pin "1") (pinfunction "1_1") (pintype "passive"))
      (node (ref "IC4") (pin "9") (pinfunction "OUT2_9") (pintype "output"))
    )
    (net (code "56") (name "Net-(IC4-OUT3)") (class "Default")
      (node (ref "FL11") (pin "1") (pinfunction "1_1") (pintype "passive"))
      (node (ref "IC4") (pin "7") (pinfunction "OUT3_7") (pintype "output"))
    )
    (net (code "57") (name "Net-(IC4-OUT4)") (class "Default")
      (node (ref "FL12") (pin "1") (pinfunction "1_1") (pintype "passive"))
      (node (ref "IC4") (pin "6") (pinfunction "OUT4_6") (pintype "output"))
    )
    (net (code "58") (name "Net-(MOT1A-S)") (class "Default")
      (node (ref "FL1") (pin "3") (pinfunction "3_3") (pintype "passive"))
      (node (ref "MOT1") (pin "1") (pinfunction "S_1") (pintype "passive"))
    )
    (net (code "59") (name "Net-(MOT1B-S)") (class "Default")
      (node (ref "FL2") (pin "3") (pinfunction "3_3") (pintype "passive"))
      (node (ref "MOT1") (pin "2") (pinfunction "S_2") (pintype "passive"))
    )
    (net (code "60") (name "Net-(MOT2A-S)") (class "Default")
      (node (ref "FL4") (pin "3") (pinfunction "3_3") (pintype "passive"))
      (node (ref "MOT2") (pin "1") (pinfunction "S_1") (pintype "passive"))
    )
    (net (code "61") (name "Net-(MOT2B-S)") (class "Default")
      (node (ref "FL3") (pin "3") (pinfunction "3_3") (pintype "passive"))
      (node (ref "MOT2") (pin "2") (pinfunction "S_2") (pintype "passive"))
    )
    (net (code "62") (name "Net-(MOT3A-S)") (class "Default")
      (node (ref "FL6") (pin "3") (pinfunction "3_3") (pintype "passive"))
      (node (ref "MOT3") (pin "1") (pinfunction "S_1") (pintype "passive"))
    )
    (net (code "63") (name "Net-(MOT3B-S)") (class "Default")
      (node (ref "FL5") (pin "3") (pinfunction "3_3") (pintype "passive"))
      (node (ref "MOT3") (pin "2") (pinfunction "S_2") (pintype "passive"))
    )
    (net (code "64") (name "Net-(MOT4A-S)") (class "Default")
      (node (ref "FL8") (pin "3") (pinfunction "3_3") (pintype "passive"))
      (node (ref "MOT4") (pin "1") (pinfunction "S_1") (pintype "passive"))
    )
    (net (code "65") (name "Net-(MOT4B-S)") (class "Default")
      (node (ref "FL7") (pin "3") (pinfunction "3_3") (pintype "passive"))
      (node (ref "MOT4") (pin "2") (pinfunction "S_2") (pintype "passive"))
    )
    (net (code "66") (name "Net-(MOT5A-S)") (class "Default")
      (node (ref "FL10") (pin "3") (pinfunction "3_3") (pintype "passive"))
      (node (ref "MOT5") (pin "1") (pinfunction "S_1") (pintype "passive"))
    )
    (net (code "67") (name "Net-(MOT5B-S)") (class "Default")
      (node (ref "FL9") (pin "3") (pinfunction "3_3") (pintype "passive"))
      (node (ref "MOT5") (pin "2") (pinfunction "S_2") (pintype "passive"))
    )
    (net (code "68") (name "Net-(MOT6A-S)") (class "Default")
      (node (ref "FL12") (pin "3") (pinfunction "3_3") (pintype "passive"))
      (node (ref "MOT6") (pin "1") (pinfunction "S_1") (pintype "passive"))
    )
    (net (code "69") (name "Net-(MOT6B-S)") (class "Default")
      (node (ref "FL11") (pin "3") (pinfunction "3_3") (pintype "passive"))
      (node (ref "MOT6") (pin "2") (pinfunction "S_2") (pintype "passive"))
    )
    (net (code "70") (name "Net-(OV7670-PadXCLK)") (class "Default")
      (node (ref "OV7670") (pin "XCLK") (pinfunction "XCLK_XCLK") (pintype "bidirectional"))
      (node (ref "R22") (pin "2") (pinfunction "2_2") (pintype "passive"))
      (node (ref "R23") (pin "1") (pinfunction "1_1") (pintype "passive"))
    )
    (net (code "71") (name "Net-(R1-Pad2)") (class "Default")
      (node (ref "R1") (pin "2") (pinfunction "2_2") (pintype "passive"))
      (node (ref "R2") (pin "2") (pinfunction "2_2") (pintype "passive"))
      (node (ref "R3") (pin "2") (pinfunction "2_2") (pintype "passive"))
    )
    (net (code "72") (name "Net-(R3-Pad1)") (class "Default")
      (node (ref "R3") (pin "1") (pinfunction "1_1") (pintype "passive"))
      (node (ref "R4") (pin "2") (pinfunction "2_2") (pintype "passive"))
      (node (ref "R5") (pin "2") (pinfunction "2_2") (pintype "passive"))
    )
    (net (code "73") (name "Net-(R5-Pad1)") (class "Default")
      (node (ref "R5") (pin "1") (pinfunction "1_1") (pintype "passive"))
      (node (ref "R6") (pin "2") (pinfunction "2_2") (pintype "passive"))
      (node (ref "R7") (pin "2") (pinfunction "2_2") (pintype "passive"))
    )
    (net (code "74") (name "Net-(R7-Pad1)") (class "Default")
      (node (ref "R7") (pin "1") (pinfunction "1_1") (pintype "passive"))
      (node (ref "R8") (pin "2") (pinfunction "2_2") (pintype "passive"))
      (node (ref "R9") (pin "2") (pinfunction "2_2") (pintype "passive"))
    )
    (net (code "75") (name "Net-(R10-Pad2)") (class "Default")
      (node (ref "R10") (pin "2") (pinfunction "2_2") (pintype "passive"))
      (node (ref "R11") (pin "2") (pinfunction "2_2") (pintype "passive"))
      (node (ref "R9") (pin "1") (pinfunction "1_1") (pintype "passive"))
    )
    (net (code "76") (name "Net-(R11-Pad1)") (class "Default")
      (node (ref "R11") (pin "1") (pinfunction "1_1") (pintype "passive"))
      (node (ref "R12") (pin "2") (pinfunction "2_2") (pintype "passive"))
      (node (ref "R13") (pin "2") (pinfunction "2_2") (pintype "passive"))
    )
    (net (code "77") (name "Net-(R13-Pad1)") (class "Default")
      (node (ref "R13") (pin "1") (pinfunction "1_1") (pintype "passive"))
      (node (ref "R14") (pin "2") (pinfunction "2_2") (pintype "passive"))
      (node (ref "R15") (pin "2") (pinfunction "2_2") (pintype "passive"))
    )
    (net (code "78") (name "OV_D0") (class "Default")
      (node (ref "ARDUINO-MEGA1") (pin "37") (pinfunction "37_37") (pintype "bidirectional"))
      (node (ref "OV7670") (pin "D0") (pinfunction "D0_D0") (pintype "bidirectional"))
    )
    (net (code "79") (name "OV_D1") (class "Default")
      (node (ref "ARDUINO-MEGA1") (pin "36") (pinfunction "36_36") (pintype "bidirectional"))
      (node (ref "OV7670") (pin "D1") (pinfunction "D1_D1") (pintype "bidirectional"))
    )
    (net (code "80") (name "OV_D2") (class "Default")
      (node (ref "ARDUINO-MEGA1") (pin "35") (pinfunction "35_35") (pintype "bidirectional"))
      (node (ref "OV7670") (pin "D2") (pinfunction "D2_D2") (pintype "bidirectional"))
    )
    (net (code "81") (name "OV_D3") (class "Default")
      (node (ref "ARDUINO-MEGA1") (pin "34") (pinfunction "34_34") (pintype "bidirectional"))
      (node (ref "OV7670") (pin "D3") (pinfunction "D3_D3") (pintype "bidirectional"))
    )
    (net (code "82") (name "OV_D4") (class "Default")
      (node (ref "ARDUINO-MEGA1") (pin "33") (pinfunction "33_33") (pintype "bidirectional"))
      (node (ref "OV7670") (pin "D4") (pinfunction "D4_D4") (pintype "bidirectional"))
    )
    (net (code "83") (name "OV_D5") (class "Default")
      (node (ref "ARDUINO-MEGA1") (pin "32") (pinfunction "32_32") (pintype "bidirectional"))
      (node (ref "OV7670") (pin "D5") (pinfunction "D5_D5") (pintype "bidirectional"))
    )
    (net (code "84") (name "OV_D6") (class "Default")
      (node (ref "ARDUINO-MEGA1") (pin "31") (pinfunction "31_31") (pintype "bidirectional"))
      (node (ref "OV7670") (pin "D6") (pinfunction "D6_D6") (pintype "bidirectional"))
    )
    (net (code "85") (name "OV_D7") (class "Default")
      (node (ref "ARDUINO-MEGA1") (pin "30") (pinfunction "30_30") (pintype "bidirectional"))
      (node (ref "OV7670") (pin "D7") (pinfunction "D7_D7") (pintype "bidirectional"))
    )
    (net (code "86") (name "PCLK") (class "Default")
      (node (ref "ARDUINO-MEGA1") (pin "7") (pinfunction "7_7") (pintype "bidirectional"))
      (node (ref "OV7670") (pin "PCLK") (pinfunction "PCLK_PCLK") (pintype "bidirectional"))
    )
    (net (code "87") (name "RX2") (class "Default")
      (node (ref "ARDUINO-MEGA1") (pin "RX2-17") (pinfunction "RX2-17_RX2-17") (pintype "bidirectional"))
      (node (ref "ESP-01S") (pin "2") (pinfunction "2_2") (pintype "passive"))
    )
    (net (code "88") (name "SCL") (class "Default")
      (node (ref "ARDUINO-MEGA1") (pin "SCL-21") (pinfunction "SCL-21_SCL-21") (pintype "bidirectional"))
      (node (ref "OV7670") (pin "SCL") (pinfunction "SCL_SCL") (pintype "bidirectional"))
      (node (ref "R20") (pin "1") (pinfunction "1_1") (pintype "passive"))
    )
    (net (code "89") (name "SDA") (class "Default")
      (node (ref "ARDUINO-MEGA1") (pin "SDA-20") (pinfunction "SDA-20_SDA-20") (pintype "bidirectional"))
      (node (ref "OV7670") (pin "SDA") (pinfunction "SDA_SDA") (pintype "bidirectional"))
      (node (ref "R21") (pin "1") (pinfunction "1_1") (pintype "passive"))
    )
    (net (code "90") (name "SDCARD-CS") (class "Default")
      (node (ref "ARDUINO-MEGA1") (pin "53") (pinfunction "53_53") (pintype "bidirectional"))
      (node (ref "SDCARD") (pin "1") (pinfunction "1_1") (pintype "passive"))
    )
    (net (code "91") (name "SDCARD-MISO") (class "Default")
      (node (ref "ARDUINO-MEGA1") (pin "50") (pinfunction "50_50") (pintype "bidirectional"))
      (node (ref "SDCARD") (pin "4") (pinfunction "1_4") (pintype "passive"))
    )
    (net (code "92") (name "SDCARD-MOSI") (class "Default")
      (node (ref "ARDUINO-MEGA1") (pin "51") (pinfunction "51_51") (pintype "bidirectional"))
      (node (ref "SDCARD") (pin "3") (pinfunction "1_3") (pintype "passive"))
    )
    (net (code "93") (name "SDCARD-SCK") (class "Default")
      (node (ref "ARDUINO-MEGA1") (pin "52") (pinfunction "52_52") (pintype "bidirectional"))
      (node (ref "SDCARD") (pin "2") (pinfunction "1_2") (pintype "passive"))
    )
    (net (code "94") (name "SENS0") (class "Default")
      (node (ref "ARDUINO-MEGA1") (pin "A0") (pinfunction "A0_A0") (pintype "bidirectional"))
      (node (ref "R30") (pin "2") (pinfunction "2_2") (pintype "passive"))
      (node (ref "S1") (pin "2") (pinfunction "1_2") (pintype "passive"))
    )
    (net (code "95") (name "SENS1") (class "Default")
      (node (ref "ARDUINO-MEGA1") (pin "A1") (pinfunction "A1_A1") (pintype "bidirectional"))
      (node (ref "R31") (pin "2") (pinfunction "2_2") (pintype "passive"))
      (node (ref "S1") (pin "3") (pinfunction "1_3") (pintype "passive"))
    )
    (net (code "96") (name "SENS2") (class "Default")
      (node (ref "ARDUINO-MEGA1") (pin "A2") (pinfunction "A2_A2") (pintype "bidirectional"))
      (node (ref "R33") (pin "2") (pinfunction "2_2") (pintype "passive"))
      (node (ref "S2") (pin "2") (pinfunction "1_2") (pintype "passive"))
    )
    (net (code "97") (name "SENS3") (class "Default")
      (node (ref "ARDUINO-MEGA1") (pin "A3") (pinfunction "A3_A3") (pintype "bidirectional"))
      (node (ref "R34") (pin "2") (pinfunction "2_2") (pintype "passive"))
      (node (ref "S2") (pin "3") (pinfunction "1_3") (pintype "passive"))
    )
    (net (code "98") (name "SENS4") (class "Default")
      (node (ref "ARDUINO-MEGA1") (pin "A4") (pinfunction "A4_A4") (pintype "bidirectional"))
      (node (ref "R36") (pin "2") (pinfunction "2_2") (pintype "passive"))
      (node (ref "S3") (pin "2") (pinfunction "1_2") (pintype "passive"))
    )
    (net (code "99") (name "SENS5") (class "Default")
      (node (ref "ARDUINO-MEGA1") (pin "A5") (pinfunction "A5_A5") (pintype "bidirectional"))
      (node (ref "R37") (pin "2") (pinfunction "2_2") (pintype "passive"))
      (node (ref "S3") (pin "3") (pinfunction "1_3") (pintype "passive"))
    )
    (net (code "100") (name "SENS6") (class "Default")
      (node (ref "ARDUINO-MEGA1") (pin "A6") (pinfunction "A6_A6") (pintype "bidirectional"))
      (node (ref "R39") (pin "2") (pinfunction "2_2") (pintype "passive"))
      (node (ref "S4") (pin "2") (pinfunction "1_2") (pintype "passive"))
    )
    (net (code "101") (name "SENS7") (class "Default")
      (node (ref "ARDUINO-MEGA1") (pin "A7") (pinfunction "A7_A7") (pintype "bidirectional"))
      (node (ref "R40") (pin "2") (pinfunction "2_2") (pintype "passive"))
      (node (ref "S4") (pin "3") (pinfunction "1_3") (pintype "passive"))
    )
    (net (code "102") (name "SENS8") (class "Default")
      (node (ref "ARDUINO-MEGA1") (pin "A8") (pinfunction "A8_A8") (pintype "bidirectional"))
      (node (ref "R42") (pin "2") (pinfunction "2_2") (pintype "passive"))
      (node (ref "S5") (pin "2") (pinfunction "1_2") (pintype "passive"))
    )
    (net (code "103") (name "SENS9") (class "Default")
      (node (ref "ARDUINO-MEGA1") (pin "A9") (pinfunction "A9_A9") (pintype "bidirectional"))
      (node (ref "R43") (pin "2") (pinfunction "2_2") (pintype "passive"))
      (node (ref "S5") (pin "3") (pinfunction "1_3") (pintype "passive"))
    )
    (net (code "104") (name "SENS10") (class "Default")
      (node (ref "ARDUINO-MEGA1") (pin "A10") (pinfunction "A10_A10") (pintype "bidirectional"))
      (node (ref "R45") (pin "2") (pinfunction "2_2") (pintype "passive"))
      (node (ref "S6") (pin "2") (pinfunction "1_2") (pintype "passive"))
    )
    (net (code "105") (name "SENS11") (class "Default")
      (node (ref "ARDUINO-MEGA1") (pin "A11") (pinfunction "A11_A11") (pintype "bidirectional"))
      (node (ref "R46") (pin "2") (pinfunction "2_2") (pintype "passive"))
      (node (ref "S6") (pin "3") (pinfunction "1_3") (pintype "passive"))
    )
    (net (code "106") (name "SENS12") (class "Default")
      (node (ref "ARDUINO-MEGA1") (pin "A12") (pinfunction "A12_A12") (pintype "bidirectional"))
      (node (ref "R48") (pin "2") (pinfunction "2_2") (pintype "passive"))
      (node (ref "S7") (pin "2") (pinfunction "1_2") (pintype "passive"))
    )
    (net (code "107") (name "SENS13") (class "Default")
      (node (ref "ARDUINO-MEGA1") (pin "A13") (pinfunction "A13_A13") (pintype "bidirectional"))
      (node (ref "R49") (pin "2") (pinfunction "2_2") (pintype "passive"))
      (node (ref "S7") (pin "3") (pinfunction "1_3") (pintype "passive"))
    )
    (net (code "108") (name "SENS14") (class "Default")
      (node (ref "ARDUINO-MEGA1") (pin "A14") (pinfunction "A14_A14") (pintype "bidirectional"))
      (node (ref "R51") (pin "2") (pinfunction "2_2") (pintype "passive"))
      (node (ref "S8") (pin "2") (pinfunction "1_2") (pintype "passive"))
    )
    (net (code "109") (name "SENS15") (class "Default")
      (node (ref "ARDUINO-MEGA1") (pin "A15") (pinfunction "A15_A15") (pintype "bidirectional"))
      (node (ref "R52") (pin "2") (pinfunction "2_2") (pintype "passive"))
      (node (ref "S8") (pin "3") (pinfunction "1_3") (pintype "passive"))
    )
    (net (code "110") (name "TX2") (class "Default")
      (node (ref "ARDUINO-MEGA1") (pin "TX2-16") (pinfunction "TX2-16_TX2-16") (pintype "bidirectional"))
      (node (ref "R25") (pin "1") (pinfunction "1_1") (pintype "passive"))
    )
    (net (code "111") (name "VSYNC") (class "Default")
      (node (ref "ARDUINO-MEGA1") (pin "9") (pinfunction "9_9") (pintype "bidirectional"))
      (node (ref "OV7670") (pin "VSYNC") (pinfunction "VSYNC_VSYNC") (pintype "bidirectional"))
    )
    (net (code "112") (name "XCLK") (class "Default")
      (node (ref "ARDUINO-MEGA1") (pin "6") (pinfunction "6_6") (pintype "bidirectional"))
      (node (ref "R23") (pin "2") (pinfunction "2_2") (pintype "passive"))
    )
    (net (code "113") (name "unconnected-(ARDUINO-MEGA1-Pad5V_2)") (class "Default")
      (node (ref "ARDUINO-MEGA1") (pin "5V_2") (pinfunction "5V_2_5V_2") (pintype "bidirectional"))
    )
    (net (code "114") (name "unconnected-(ARDUINO-MEGA1-Pad5V_3)") (class "Default")
      (node (ref "ARDUINO-MEGA1") (pin "5V_3") (pinfunction "5V_3_5V_3") (pintype "bidirectional"))
    )
    (net (code "115") (name "unconnected-(ARDUINO-MEGA1-Pad23)") (class "Default")
      (node (ref "ARDUINO-MEGA1") (pin "23") (pinfunction "23_23") (pintype "bidirectional"))
    )
    (net (code "116") (name "unconnected-(ARDUINO-MEGA1-Pad25)") (class "Default")
      (node (ref "ARDUINO-MEGA1") (pin "25") (pinfunction "25_25") (pintype "bidirectional"))
    )
    (net (code "117") (name "unconnected-(ARDUINO-MEGA1-Pad27)") (class "Default")
      (node (ref "ARDUINO-MEGA1") (pin "27") (pinfunction "27_27") (pintype "bidirectional"))
    )
    (net (code "118") (name "unconnected-(ARDUINO-MEGA1-Pad29)") (class "Default")
      (node (ref "ARDUINO-MEGA1") (pin "29") (pinfunction "29_29") (pintype "bidirectional"))
    )
    (net (code "119") (name "unconnected-(ARDUINO-MEGA1-Pad38)") (class "Default")
      (node (ref "ARDUINO-MEGA1") (pin "38") (pinfunction "38_38") (pintype "bidirectional"))
    )
    (net (code "120") (name "unconnected-(ARDUINO-MEGA1-Pad39)") (class "Default")
      (node (ref "ARDUINO-MEGA1") (pin "39") (pinfunction "39_39") (pintype "bidirectional"))
    )
    (net (code "121") (name "unconnected-(ARDUINO-MEGA1-Pad41)") (class "Default")
      (node (ref "ARDUINO-MEGA1") (pin "41") (pinfunction "41_41") (pintype "bidirectional"))
    )
    (net (code "122") (name "unconnected-(ARDUINO-MEGA1-PadAREF)") (class "Default")
      (node (ref "ARDUINO-MEGA1") (pin "AREF") (pinfunction "AREF_AREF") (pintype "bidirectional"))
    )
    (net (code "123") (name "unconnected-(ARDUINO-MEGA1-PadGND_1)") (class "Default")
      (node (ref "ARDUINO-MEGA1") (pin "GND_1") (pinfunction "GND_1_GND_1") (pintype "bidirectional"))
    )
    (net (code "124") (name "unconnected-(ARDUINO-MEGA1-PadGND_2)") (class "Default")
      (node (ref "ARDUINO-MEGA1") (pin "GND_2") (pinfunction "GND_2_GND_2") (pintype "bidirectional"))
    )
    (net (code "125") (name "unconnected-(ARDUINO-MEGA1-PadGND_3)") (class "Default")
      (node (ref "ARDUINO-MEGA1") (pin "GND_3") (pinfunction "GND_3_GND_3") (pintype "bidirectional"))
    )
    (net (code "126") (name "unconnected-(ARDUINO-MEGA1-PadIOREF)") (class "Default")
      (node (ref "ARDUINO-MEGA1") (pin "IOREF") (pinfunction "IOREF_IOREF") (pintype "bidirectional"))
    )
    (net (code "127") (name "unconnected-(ARDUINO-MEGA1-PadN.C.)") (class "Default")
      (node (ref "ARDUINO-MEGA1") (pin "N.C.") (pinfunction "N.C._N.C.") (pintype "bidirectional"))
    )
    (net (code "128") (name "unconnected-(ARDUINO-MEGA1-PadRESET)") (class "Default")
      (node (ref "ARDUINO-MEGA1") (pin "RESET") (pinfunction "RESET_RESET") (pintype "bidirectional"))
    )
    (net (code "129") (name "unconnected-(ARDUINO-MEGA1-PadRX0-0)") (class "Default")
      (node (ref "ARDUINO-MEGA1") (pin "RX0-0") (pinfunction "RX0-0_RX0-0") (pintype "bidirectional"))
    )
    (net (code "130") (name "unconnected-(ARDUINO-MEGA1-PadRX3-15)") (class "Default")
      (node (ref "ARDUINO-MEGA1") (pin "RX3-15") (pinfunction "RX3-15_RX3-15") (pintype "bidirectional"))
    )
    (net (code "131") (name "unconnected-(ARDUINO-MEGA1-PadSCL)") (class "Default")
      (node (ref "ARDUINO-MEGA1") (pin "SCL") (pinfunction "SCL_SCL") (pintype "bidirectional"))
    )
    (net (code "132") (name "unconnected-(ARDUINO-MEGA1-PadSDA)") (class "Default")
      (node (ref "ARDUINO-MEGA1") (pin "SDA") (pinfunction "SDA_SDA") (pintype "bidirectional"))
    )
    (net (code "133") (name "unconnected-(ARDUINO-MEGA1-PadTX0-1)") (class "Default")
      (node (ref "ARDUINO-MEGA1") (pin "TX0-1") (pinfunction "TX0-1_TX0-1") (pintype "bidirectional"))
    )
    (net (code "134") (name "unconnected-(ARDUINO-MEGA1-PadTX3-14)") (class "Default")
      (node (ref "ARDUINO-MEGA1") (pin "TX3-14") (pinfunction "TX3-14_TX3-14") (pintype "bidirectional"))
    )
    (net (code "135") (name "unconnected-(ARDUINO-MEGA1-PadVIN)") (class "Default")
      (node (ref "ARDUINO-MEGA1") (pin "VIN") (pinfunction "VIN_VIN") (pintype "bidirectional"))
    )
    (net (code "136") (name "unconnected-(ESP-01S-Pad3)") (class "Default")
      (node (ref "ESP-01S") (pin "3") (pinfunction "3_3") (pintype "passive"))
    )
    (net (code "137") (name "unconnected-(ESP-01S-Pad5)") (class "Default")
      (node (ref "ESP-01S") (pin "5") (pinfunction "5_5") (pintype "passive"))
    )
    (net (code "138") (name "{slash}DAC_SD") (class "Default")
      (node (ref "ARDUINO-MEGA1") (pin "40") (pinfunction "40_40") (pintype "bidirectional"))
      (node (ref "IC1") (pin "1") (pinfunction "/SHUTDOWN_1") (pintype "bidirectional"))
      (node (ref "R17") (pin "2") (pinfunction "2_2") (pintype "passive"))
    )
    (net (code "139") (name "{slash}ESP_RST") (class "Default")
      (node (ref "ARDUINO-MEGA1") (pin "RX1-19") (pinfunction "RX1-19_RX1-19") (pintype "bidirectional"))
      (node (ref "R27") (pin "2") (pinfunction "2_2") (pintype "passive"))
    )
  )
)
